# buttons.net
KiCad netlist of a schematic drawn in Altium Designer
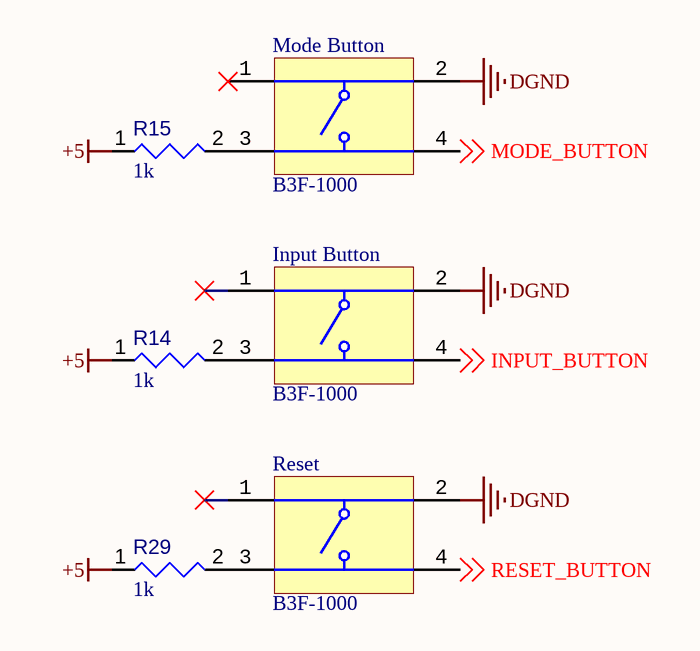
[diagram p0: buttons.SchDoc]

(export (version "E")
  (design (tool "Eeschema 10.0.6"))
  (components
    (comp (ref "Input Button")
      (value "B3F-1000")
      (footprint "OMRON-B3F-1000-4_V")
      (description "Tactile Switch, SPST-NO, 0.05 A, 24 V, -25 to 70 degC, 4-Pin THD, RoHS, Bulk")
      (fields (field (name "MANUFACTURER") "Omron Electronic Components"))
      (libsource (lib "Americas- CUAir- Cornell University") (part "SW-SPST-4_A"))
    )
    (comp (ref "Mode Button")
      (value "B3F-1000")
      (footprint "OMRON-B3F-1000-4_V")
      (description "Tactile Switch, SPST-NO, 0.05 A, 24 V, -25 to 70 degC, 4-Pin THD, RoHS, Bulk")
      (fields (field (name "MANUFACTURER") "Omron Electronic Components"))
      (libsource (lib "Americas- CUAir- Cornell University") (part "SW-SPST-4_A"))
    )
    (comp (ref "R14")
      (value "1k")
      (footprint "RESC0402(1005)_L")
      (description "Chip Resistor, 1 kOhms, +/-5 %, 63 mW, -55 to 155 degC, 0402")
      (fields (field (name "TOLERANCE") "5%") (field (name "POWER") "63mW"))
      (libsource (lib "Americas- CUAir- Cornell University") (part "RES-2"))
    )
    (comp (ref "R15")
      (value "1k")
      (footprint "RESC0402(1005)_L")
      (description "Chip Resistor, 1 kOhms, +/-5 %, 63 mW, -55 to 155 degC, 0402")
      (fields (field (name "TOLERANCE") "5%") (field (name "POWER") "63mW"))
      (libsource (lib "Americas- CUAir- Cornell University") (part "RES-2"))
    )
    (comp (ref "R29")
      (value "1k")
      (footprint "RESC0402(1005)_L")
      (description "Chip Resistor, 1 kOhms, +/-5 %, 63 mW, -55 to 155 degC, 0402")
      (fields (field (name "TOLERANCE") "5%") (field (name "POWER") "63mW"))
      (libsource (lib "Americas- CUAir- Cornell University") (part "RES-2"))
    )
    (comp (ref "Reset")
      (value "B3F-1000")
      (footprint "OMRON-B3F-1000-4_V")
      (description "Tactile Switch, SPST-NO, 0.05 A, 24 V, -25 to 70 degC, 4-Pin THD, RoHS, Bulk")
      (fields (field (name "MANUFACTURER") "Omron Electronic Components"))
      (libsource (lib "Americas- CUAir- Cornell University") (part "SW-SPST-4_A"))
    )
  )
  (nets
    (net (code "1") (name "+5") (class "Default")
      (node (ref "R14") (pin "1") (pinfunction "1_1") (pintype "passive"))
      (node (ref "R15") (pin "1") (pinfunction "1_1") (pintype "passive"))
      (node (ref "R29") (pin "1") (pinfunction "1_1") (pintype "passive"))
    )
    (net (code "2") (name "DGND") (class "Default")
      (node (ref "Input Button") (pin "2") (pinfunction "2_2") (pintype "passive"))
      (node (ref "Mode Button") (pin "2") (pinfunction "2_2") (pintype "passive"))
      (node (ref "Reset") (pin "2") (pinfunction "2_2") (pintype "passive"))
    )
    (net (code "3") (name "INPUT_BUTTON") (class "Default")
      (node (ref "Input Button") (pin "4") (pinfunction "4_4") (pintype "passive"))
    )
    (net (code "4") (name "MODE_BUTTON") (class "Default")
      (node (ref "Mode Button") (pin "4") (pinfunction "4_4") (pintype "passive"))
    )
    (net (code "5") (name "Net-(Input Button-Pad3)") (class "Default")
      (node (ref "Input Button") (pin "3") (pinfunction "3_3") (pintype "passive"))
      (node (ref "R14") (pin "2") (pinfunction "2_2") (pintype "passive"))
    )
    (net (code "6") (name "Net-(Mode Button-Pad3)") (class "Default")
      (node (ref "Mode Button") (pin "3") (pinfunction "3_3") (pintype "passive"))
      (node (ref "R15") (pin "2") (pinfunction "2_2") (pintype "passive"))
    )
    (net (code "7") (name "Net-(R29-Pad2)") (class "Default")
      (node (ref "R29") (pin "2") (pinfunction "2_2") (pintype "passive"))
      (node (ref "Reset") (pin "3") (pinfunction "3_3") (pintype "passive"))
    )
    (net (code "8") (name "RESET_BUTTON") (class "Default")
      (node (ref "Reset") (pin "4") (pinfunction "4_4") (pintype "passive"))
    )
    (net (code "9") (name "unconnected-(Input Button-Pad1)") (class "Default")
      (node (ref "Input Button") (pin "1") (pinfunction "1_1") (pintype "passive+no_connect"))
    )
    (net (code "10") (name "unconnected-(Mode Button-Pad1)") (class "Default")
      (node (ref "Mode Button") (pin "1") (pinfunction "1_1") (pintype "passive+no_connect"))
    )
    (net (code "11") (name "unconnected-(Reset-Pad1)") (class "Default")
      (node (ref "Reset") (pin "1") (pinfunction "1_1") (pintype "passive+no_connect"))
    )
  )
)
